# I2C_SENSOR.net
KiCad netlist of a schematic drawn in Altium Designer
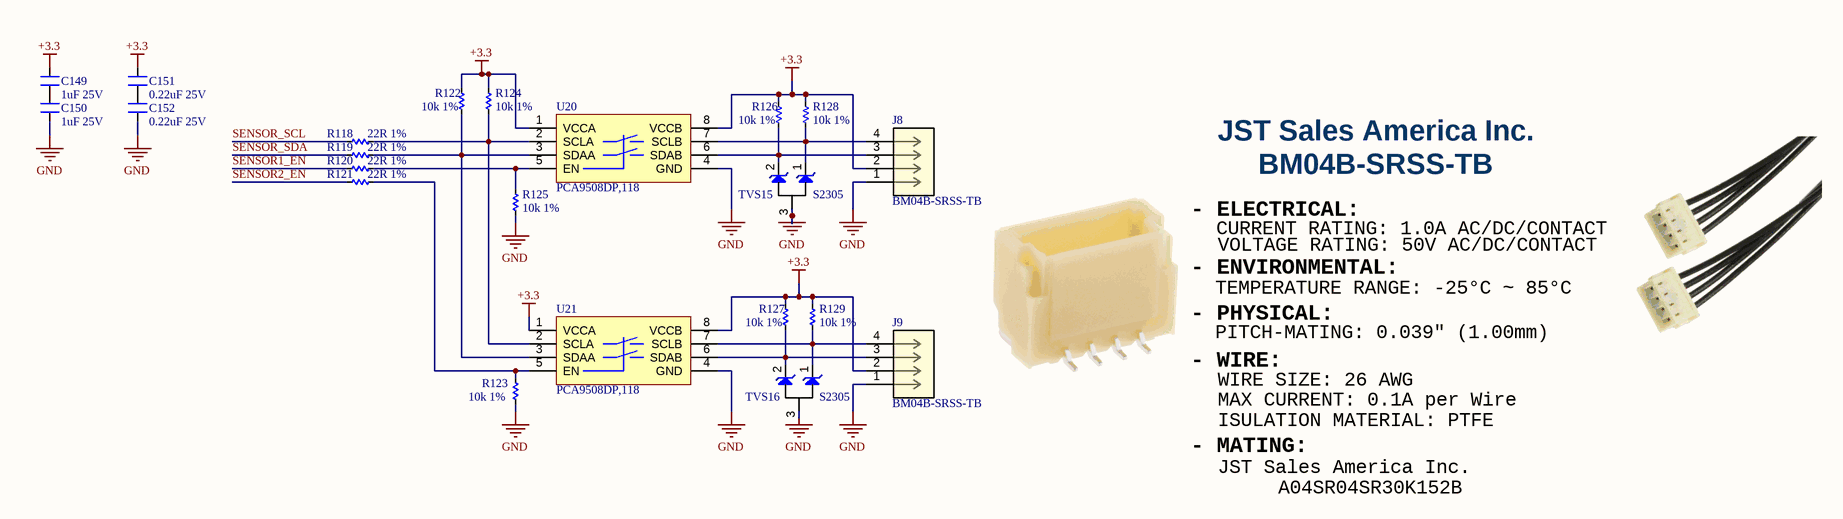
[diagram p0: I2C_SENSOR.SchDoc]

(export (version "E")
  (design (tool "Eeschema 10.0.6"))
  (components
    (comp (ref "C149")
      (value "1uF 25V")
      (footprint "CN-SMD-0603-EXP-V101")
      (libsource (lib "Sang_library") (part "Capacitors"))
    )
    (comp (ref "C150")
      (value "1uF 25V")
      (footprint "CN-SMD-0603-EXP-V101")
      (libsource (lib "Sang_library") (part "Capacitors"))
    )
    (comp (ref "C151")
      (value "0.22uF 25V")
      (footprint "CN-SMD-0603-EXP-V101")
      (libsource (lib "Sang_library") (part "Capacitors"))
    )
    (comp (ref "C152")
      (value "0.22uF 25V")
      (footprint "CN-SMD-0603-EXP-V101")
      (libsource (lib "Sang_library") (part "Capacitors"))
    )
    (comp (ref "J8")
      (value "BM04B-SRSS-TB")
      (footprint "BM04B-SRSS-TB")
      (description "CONN HEADER SMD 4POS 1MM")
      (libsource (lib "EXP_V1") (part "BM04B-SRSS-TB"))
    )
    (comp (ref "J9")
      (value "BM04B-SRSS-TB")
      (footprint "BM04B-SRSS-TB")
      (description "CONN HEADER SMD 4POS 1MM")
      (libsource (lib "EXP_V1") (part "BM04B-SRSS-TB"))
    )
    (comp (ref "R118")
      (value "22R 1%")
      (footprint "RES-SMD-0603-EXP-V101")
      (description "SMD")
      (fields
        (field (name "MANUFACTURER") "Generic Components")
        (field (name "PUBLISHER") "Altium Hobart Technology Centre")
      )
      (libsource (lib "Sang_library") (part "Res SMD"))
    )
    (comp (ref "R119")
      (value "22R 1%")
      (footprint "RES-SMD-0603-EXP-V101")
      (description "SMD")
      (fields
        (field (name "MANUFACTURER") "Generic Components")
        (field (name "PUBLISHER") "Altium Hobart Technology Centre")
      )
      (libsource (lib "Sang_library") (part "Res SMD"))
    )
    (comp (ref "R120")
      (value "22R 1%")
      (footprint "RES-SMD-0603-EXP-V101")
      (description "SMD")
      (fields
        (field (name "MANUFACTURER") "Generic Components")
        (field (name "PUBLISHER") "Altium Hobart Technology Centre")
      )
      (libsource (lib "Sang_library") (part "Res SMD"))
    )
    (comp (ref "R121")
      (value "22R 1%")
      (footprint "RES-SMD-0603-EXP-V101")
      (description "SMD")
      (fields
        (field (name "MANUFACTURER") "Generic Components")
        (field (name "PUBLISHER") "Altium Hobart Technology Centre")
      )
      (libsource (lib "Sang_library") (part "Res SMD"))
    )
    (comp (ref "R122")
      (value "10k 1%")
      (footprint "RES-SMD-0603-EXP-V101")
      (description "SMD")
      (fields
        (field (name "MANUFACTURER") "Generic Components")
        (field (name "PUBLISHER") "Altium Hobart Technology Centre")
      )
      (libsource (lib "Sang_library") (part "Res SMD"))
    )
    (comp (ref "R123")
      (value "10k 1%")
      (footprint "RES-SMD-0603-EXP-V101")
      (description "SMD")
      (fields
        (field (name "MANUFACTURER") "Generic Components")
        (field (name "PUBLISHER") "Altium Hobart Technology Centre")
      )
      (libsource (lib "Sang_library") (part "Res SMD"))
    )
    (comp (ref "R124")
      (value "10k 1%")
      (footprint "RES-SMD-0603-EXP-V101")
      (description "SMD")
      (fields
        (field (name "MANUFACTURER") "Generic Components")
        (field (name "PUBLISHER") "Altium Hobart Technology Centre")
      )
      (libsource (lib "Sang_library") (part "Res SMD"))
    )
    (comp (ref "R125")
      (value "10k 1%")
      (footprint "RES-SMD-0603-EXP-V101")
      (description "SMD")
      (fields
        (field (name "MANUFACTURER") "Generic Components")
        (field (name "PUBLISHER") "Altium Hobart Technology Centre")
      )
      (libsource (lib "Sang_library") (part "Res SMD"))
    )
    (comp (ref "R126")
      (value "10k 1%")
      (footprint "RES-SMD-0603-EXP-V101")
      (description "SMD")
      (fields
        (field (name "MANUFACTURER") "Generic Components")
        (field (name "PUBLISHER") "Altium Hobart Technology Centre")
      )
      (libsource (lib "Sang_library") (part "Res SMD"))
    )
    (comp (ref "R127")
      (value "10k 1%")
      (footprint "RES-SMD-0603-EXP-V101")
      (description "SMD")
      (fields
        (field (name "MANUFACTURER") "Generic Components")
        (field (name "PUBLISHER") "Altium Hobart Technology Centre")
      )
      (libsource (lib "Sang_library") (part "Res SMD"))
    )
    (comp (ref "R128")
      (value "10k 1%")
      (footprint "RES-SMD-0603-EXP-V101")
      (description "SMD")
      (fields
        (field (name "MANUFACTURER") "Generic Components")
        (field (name "PUBLISHER") "Altium Hobart Technology Centre")
      )
      (libsource (lib "Sang_library") (part "Res SMD"))
    )
    (comp (ref "R129")
      (value "10k 1%")
      (footprint "RES-SMD-0603-EXP-V101")
      (description "SMD")
      (fields
        (field (name "MANUFACTURER") "Generic Components")
        (field (name "PUBLISHER") "Altium Hobart Technology Centre")
      )
      (libsource (lib "Sang_library") (part "Res SMD"))
    )
    (comp (ref "TVS15")
      (value "S2305")
      (footprint "sot23-12_3")
      (description "TVS DIODE 5VWM 10.8VC SOT23")
      (libsource (lib "Sang_library") (part "S2305"))
    )
    (comp (ref "TVS16")
      (value "S2305")
      (footprint "sot23-12_3")
      (description "TVS DIODE 5VWM 10.8VC SOT23")
      (libsource (lib "Sang_library") (part "S2305"))
    )
    (comp (ref "U20")
      (value "PCA9508DP,118")
      (footprint "TSOP8")
      (libsource (lib "Sang_library") (part "PCA9508DP,118"))
    )
    (comp (ref "U21")
      (value "PCA9508DP,118")
      (footprint "TSOP8")
      (libsource (lib "Sang_library") (part "PCA9508DP,118"))
    )
  )
  (nets
    (net (code "1") (name "+3.3") (class "Default")
      (node (ref "C149") (pin "2") (pinfunction "2_2") (pintype "passive"))
      (node (ref "C151") (pin "2") (pinfunction "2_2") (pintype "passive"))
      (node (ref "J8") (pin "2") (pinfunction "2_2") (pintype "passive"))
      (node (ref "J9") (pin "2") (pinfunction "2_2") (pintype "passive"))
      (node (ref "R122") (pin "1") (pinfunction "1_1") (pintype "passive"))
      (node (ref "R124") (pin "1") (pinfunction "1_1") (pintype "passive"))
      (node (ref "R126") (pin "1") (pinfunction "1_1") (pintype "passive"))
      (node (ref "R127") (pin "1") (pinfunction "1_1") (pintype "passive"))
      (node (ref "R128") (pin "1") (pinfunction "1_1") (pintype "passive"))
      (node (ref "R129") (pin "1") (pinfunction "1_1") (pintype "passive"))
      (node (ref "U20") (pin "1") (pinfunction "VCCA_1") (pintype "passive"))
      (node (ref "U20") (pin "8") (pinfunction "VCCB_8") (pintype "passive"))
      (node (ref "U21") (pin "1") (pinfunction "VCCA_1") (pintype "passive"))
      (node (ref "U21") (pin "8") (pinfunction "VCCB_8") (pintype "passive"))
    )
    (net (code "2") (name "/SENSOR1_EN") (class "Default")
      (node (ref "R120") (pin "1") (pinfunction "1_1") (pintype "passive"))
    )
    (net (code "3") (name "/SENSOR2_EN") (class "Default")
      (node (ref "R121") (pin "1") (pinfunction "1_1") (pintype "passive"))
    )
    (net (code "4") (name "/SENSOR_SCL") (class "Default")
      (node (ref "R118") (pin "1") (pinfunction "1_1") (pintype "passive"))
    )
    (net (code "5") (name "/SENSOR_SDA") (class "Default")
      (node (ref "R119") (pin "1") (pinfunction "1_1") (pintype "passive"))
    )
    (net (code "6") (name "GND") (class "Default")
      (node (ref "C150") (pin "1") (pinfunction "1_1") (pintype "passive"))
      (node (ref "C152") (pin "1") (pinfunction "1_1") (pintype "passive"))
      (node (ref "J8") (pin "1") (pinfunction "1_1") (pintype "passive"))
      (node (ref "J9") (pin "1") (pinfunction "1_1") (pintype "passive"))
      (node (ref "R123") (pin "2") (pinfunction "2_2") (pintype "passive"))
      (node (ref "R125") (pin "2") (pinfunction "2_2") (pintype "passive"))
      (node (ref "TVS15") (pin "3") (pinfunction "3_3") (pintype "passive"))
      (node (ref "TVS16") (pin "3") (pinfunction "3_3") (pintype "passive"))
      (node (ref "U20") (pin "4") (pinfunction "GND_4") (pintype "passive"))
      (node (ref "U21") (pin "4") (pinfunction "GND_4") (pintype "passive"))
    )
    (net (code "7") (name "Net-(C149-Pad1)") (class "Default")
      (node (ref "C149") (pin "1") (pinfunction "1_1") (pintype "passive"))
      (node (ref "C150") (pin "2") (pinfunction "2_2") (pintype "passive"))
    )
    (net (code "8") (name "Net-(C151-Pad1)") (class "Default")
      (node (ref "C151") (pin "1") (pinfunction "1_1") (pintype "passive"))
      (node (ref "C152") (pin "2") (pinfunction "2_2") (pintype "passive"))
    )
    (net (code "9") (name "Net-(U20-EN)") (class "Default")
      (node (ref "R120") (pin "2") (pinfunction "2_2") (pintype "passive"))
      (node (ref "R125") (pin "1") (pinfunction "1_1") (pintype "passive"))
      (node (ref "U20") (pin "5") (pinfunction "EN_5") (pintype "passive"))
    )
    (net (code "10") (name "Net-(U20-SCLA)") (class "Default")
      (node (ref "R118") (pin "2") (pinfunction "2_2") (pintype "passive"))
      (node (ref "R124") (pin "2") (pinfunction "2_2") (pintype "passive"))
      (node (ref "U20") (pin "2") (pinfunction "SCLA_2") (pintype "passive"))
      (node (ref "U21") (pin "2") (pinfunction "SCLA_2") (pintype "passive"))
    )
    (net (code "11") (name "Net-(U20-SCLB)") (class "Default")
      (node (ref "J8") (pin "4") (pinfunction "4_4") (pintype "passive"))
      (node (ref "R128") (pin "2") (pinfunction "2_2") (pintype "passive"))
      (node (ref "TVS15") (pin "1") (pinfunction "1_1") (pintype "passive"))
      (node (ref "U20") (pin "7") (pinfunction "SCLB_7") (pintype "passive"))
    )
    (net (code "12") (name "Net-(U20-SDAA)") (class "Default")
      (node (ref "R119") (pin "2") (pinfunction "2_2") (pintype "passive"))
      (node (ref "R122") (pin "2") (pinfunction "2_2") (pintype "passive"))
      (node (ref "U20") (pin "3") (pinfunction "SDAA_3") (pintype "passive"))
      (node (ref "U21") (pin "3") (pinfunction "SDAA_3") (pintype "passive"))
    )
    (net (code "13") (name "Net-(U20-SDAB)") (class "Default")
      (node (ref "J8") (pin "3") (pinfunction "3_3") (pintype "passive"))
      (node (ref "R126") (pin "2") (pinfunction "2_2") (pintype "passive"))
      (node (ref "TVS15") (pin "2") (pinfunction "2_2") (pintype "passive"))
      (node (ref "U20") (pin "6") (pinfunction "SDAB_6") (pintype "passive"))
    )
    (net (code "14") (name "Net-(U21-EN)") (class "Default")
      (node (ref "R121") (pin "2") (pinfunction "2_2") (pintype "passive"))
      (node (ref "R123") (pin "1") (pinfunction "1_1") (pintype "passive"))
      (node (ref "U21") (pin "5") (pinfunction "EN_5") (pintype "passive"))
    )
    (net (code "15") (name "Net-(U21-SCLB)") (class "Default")
      (node (ref "J9") (pin "4") (pinfunction "4_4") (pintype "passive"))
      (node (ref "R129") (pin "2") (pinfunction "2_2") (pintype "passive"))
      (node (ref "TVS16") (pin "1") (pinfunction "1_1") (pintype "passive"))
      (node (ref "U21") (pin "7") (pinfunction "SCLB_7") (pintype "passive"))
    )
    (net (code "16") (name "Net-(U21-SDAB)") (class "Default")
      (node (ref "J9") (pin "3") (pinfunction "3_3") (pintype "passive"))
      (node (ref "R127") (pin "2") (pinfunction "2_2") (pintype "passive"))
      (node (ref "TVS16") (pin "2") (pinfunction "2_2") (pintype "passive"))
      (node (ref "U21") (pin "6") (pinfunction "SDAB_6") (pintype "passive"))
    )
  )
)
